# Matric_PCB.net
KiCad netlist of a schematic drawn in EAGLE
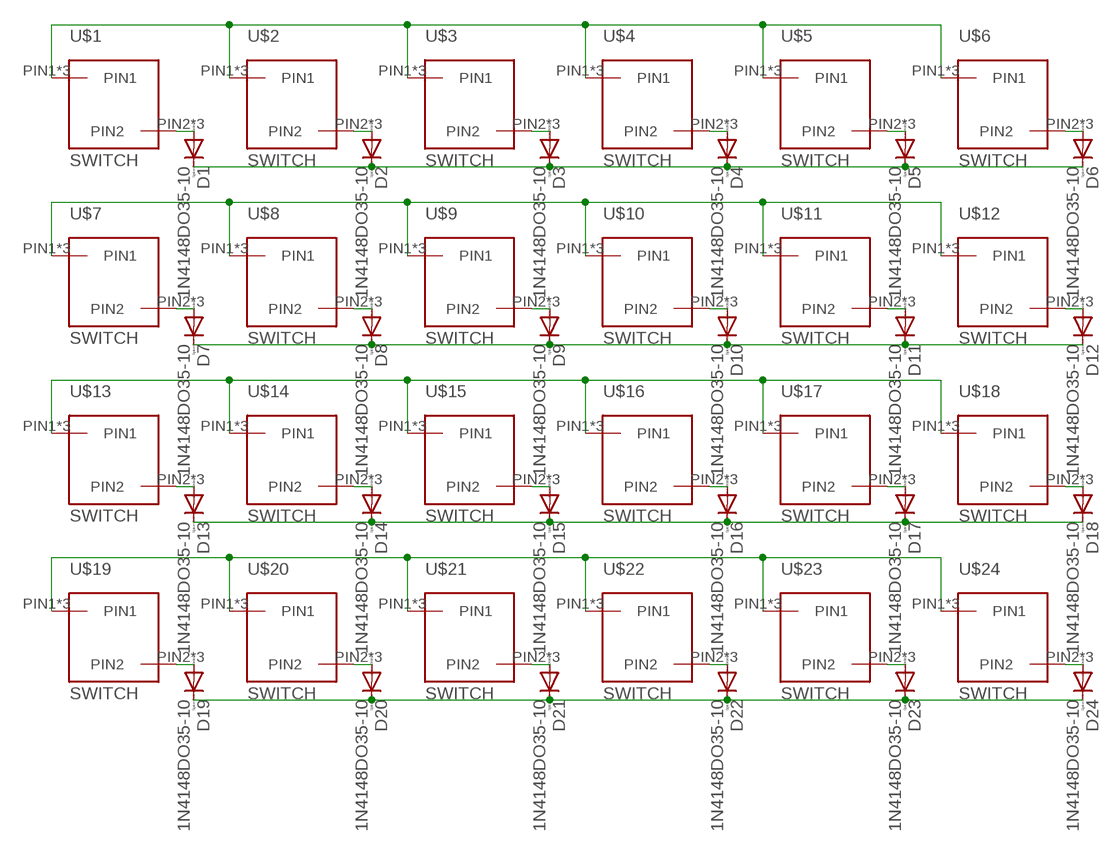
[diagram p0: schematic, sheet 1]

(export (version "E")
  (design (tool "Eeschema 10.0.6"))
  (components
    (comp (ref "D1")
      (value "1N4148DO35-10")
      (footprint "eagle-import:DO35-10")
      (libsource (lib "eagle-import") (part "1N4148DO35-10"))
    )
    (comp (ref "D2")
      (value "1N4148DO35-10")
      (footprint "eagle-import:DO35-10")
      (libsource (lib "eagle-import") (part "1N4148DO35-10"))
    )
    (comp (ref "D3")
      (value "1N4148DO35-10")
      (footprint "eagle-import:DO35-10")
      (libsource (lib "eagle-import") (part "1N4148DO35-10"))
    )
    (comp (ref "D4")
      (value "1N4148DO35-10")
      (footprint "eagle-import:DO35-10")
      (libsource (lib "eagle-import") (part "1N4148DO35-10"))
    )
    (comp (ref "D5")
      (value "1N4148DO35-10")
      (footprint "eagle-import:DO35-10")
      (libsource (lib "eagle-import") (part "1N4148DO35-10"))
    )
    (comp (ref "D6")
      (value "1N4148DO35-10")
      (footprint "eagle-import:DO35-10")
      (libsource (lib "eagle-import") (part "1N4148DO35-10"))
    )
    (comp (ref "D7")
      (value "1N4148DO35-10")
      (footprint "eagle-import:DO35-10")
      (libsource (lib "eagle-import") (part "1N4148DO35-10"))
    )
    (comp (ref "D8")
      (value "1N4148DO35-10")
      (footprint "eagle-import:DO35-10")
      (libsource (lib "eagle-import") (part "1N4148DO35-10"))
    )
    (comp (ref "D9")
      (value "1N4148DO35-10")
      (footprint "eagle-import:DO35-10")
      (libsource (lib "eagle-import") (part "1N4148DO35-10"))
    )
    (comp (ref "D10")
      (value "1N4148DO35-10")
      (footprint "eagle-import:DO35-10")
      (libsource (lib "eagle-import") (part "1N4148DO35-10"))
    )
    (comp (ref "D11")
      (value "1N4148DO35-10")
      (footprint "eagle-import:DO35-10")
      (libsource (lib "eagle-import") (part "1N4148DO35-10"))
    )
    (comp (ref "D12")
      (value "1N4148DO35-10")
      (footprint "eagle-import:DO35-10")
      (libsource (lib "eagle-import") (part "1N4148DO35-10"))
    )
    (comp (ref "D13")
      (value "1N4148DO35-10")
      (footprint "eagle-import:DO35-10")
      (libsource (lib "eagle-import") (part "1N4148DO35-10"))
    )
    (comp (ref "D14")
      (value "1N4148DO35-10")
      (footprint "eagle-import:DO35-10")
      (libsource (lib "eagle-import") (part "1N4148DO35-10"))
    )
    (comp (ref "D15")
      (value "1N4148DO35-10")
      (footprint "eagle-import:DO35-10")
      (libsource (lib "eagle-import") (part "1N4148DO35-10"))
    )
    (comp (ref "D16")
      (value "1N4148DO35-10")
      (footprint "eagle-import:DO35-10")
      (libsource (lib "eagle-import") (part "1N4148DO35-10"))
    )
    (comp (ref "D17")
      (value "1N4148DO35-10")
      (footprint "eagle-import:DO35-10")
      (libsource (lib "eagle-import") (part "1N4148DO35-10"))
    )
    (comp (ref "D18")
      (value "1N4148DO35-10")
      (footprint "eagle-import:DO35-10")
      (libsource (lib "eagle-import") (part "1N4148DO35-10"))
    )
    (comp (ref "D19")
      (value "1N4148DO35-10")
      (footprint "eagle-import:DO35-10")
      (libsource (lib "eagle-import") (part "1N4148DO35-10"))
    )
    (comp (ref "D20")
      (value "1N4148DO35-10")
      (footprint "eagle-import:DO35-10")
      (libsource (lib "eagle-import") (part "1N4148DO35-10"))
    )
    (comp (ref "D21")
      (value "1N4148DO35-10")
      (footprint "eagle-import:DO35-10")
      (libsource (lib "eagle-import") (part "1N4148DO35-10"))
    )
    (comp (ref "D22")
      (value "1N4148DO35-10")
      (footprint "eagle-import:DO35-10")
      (libsource (lib "eagle-import") (part "1N4148DO35-10"))
    )
    (comp (ref "D23")
      (value "1N4148DO35-10")
      (footprint "eagle-import:DO35-10")
      (libsource (lib "eagle-import") (part "1N4148DO35-10"))
    )
    (comp (ref "D24")
      (value "1N4148DO35-10")
      (footprint "eagle-import:DO35-10")
      (libsource (lib "eagle-import") (part "1N4148DO35-10"))
    )
    (comp (ref "U$1")
      (value "SWITCH")
      (footprint "eagle-import:SWITCH")
      (libsource (lib "eagle-import") (part "SWITCH"))
    )
    (comp (ref "U$2")
      (value "SWITCH")
      (footprint "eagle-import:SWITCH")
      (libsource (lib "eagle-import") (part "SWITCH"))
    )
    (comp (ref "U$3")
      (value "SWITCH")
      (footprint "eagle-import:SWITCH")
      (libsource (lib "eagle-import") (part "SWITCH"))
    )
    (comp (ref "U$4")
      (value "SWITCH")
      (footprint "eagle-import:SWITCH")
      (libsource (lib "eagle-import") (part "SWITCH"))
    )
    (comp (ref "U$5")
      (value "SWITCH")
      (footprint "eagle-import:SWITCH")
      (libsource (lib "eagle-import") (part "SWITCH"))
    )
    (comp (ref "U$6")
      (value "SWITCH")
      (footprint "eagle-import:SWITCH")
      (libsource (lib "eagle-import") (part "SWITCH"))
    )
    (comp (ref "U$7")
      (value "SWITCH")
      (footprint "eagle-import:SWITCH")
      (libsource (lib "eagle-import") (part "SWITCH"))
    )
    (comp (ref "U$8")
      (value "SWITCH")
      (footprint "eagle-import:SWITCH")
      (libsource (lib "eagle-import") (part "SWITCH"))
    )
    (comp (ref "U$9")
      (value "SWITCH")
      (footprint "eagle-import:SWITCH")
      (libsource (lib "eagle-import") (part "SWITCH"))
    )
    (comp (ref "U$10")
      (value "SWITCH")
      (footprint "eagle-import:SWITCH")
      (libsource (lib "eagle-import") (part "SWITCH"))
    )
    (comp (ref "U$11")
      (value "SWITCH")
      (footprint "eagle-import:SWITCH")
      (libsource (lib "eagle-import") (part "SWITCH"))
    )
    (comp (ref "U$12")
      (value "SWITCH")
      (footprint "eagle-import:SWITCH")
      (libsource (lib "eagle-import") (part "SWITCH"))
    )
    (comp (ref "U$13")
      (value "SWITCH")
      (footprint "eagle-import:SWITCH")
      (libsource (lib "eagle-import") (part "SWITCH"))
    )
    (comp (ref "U$14")
      (value "SWITCH")
      (footprint "eagle-import:SWITCH")
      (libsource (lib "eagle-import") (part "SWITCH"))
    )
    (comp (ref "U$15")
      (value "SWITCH")
      (footprint "eagle-import:SWITCH")
      (libsource (lib "eagle-import") (part "SWITCH"))
    )
    (comp (ref "U$16")
      (value "SWITCH")
      (footprint "eagle-import:SWITCH")
      (libsource (lib "eagle-import") (part "SWITCH"))
    )
    (comp (ref "U$17")
      (value "SWITCH")
      (footprint "eagle-import:SWITCH")
      (libsource (lib "eagle-import") (part "SWITCH"))
    )
    (comp (ref "U$18")
      (value "SWITCH")
      (footprint "eagle-import:SWITCH")
      (libsource (lib "eagle-import") (part "SWITCH"))
    )
    (comp (ref "U$19")
      (value "SWITCH")
      (footprint "eagle-import:SWITCH")
      (libsource (lib "eagle-import") (part "SWITCH"))
    )
    (comp (ref "U$20")
      (value "SWITCH")
      (footprint "eagle-import:SWITCH")
      (libsource (lib "eagle-import") (part "SWITCH"))
    )
    (comp (ref "U$21")
      (value "SWITCH")
      (footprint "eagle-import:SWITCH")
      (libsource (lib "eagle-import") (part "SWITCH"))
    )
    (comp (ref "U$22")
      (value "SWITCH")
      (footprint "eagle-import:SWITCH")
      (libsource (lib "eagle-import") (part "SWITCH"))
    )
    (comp (ref "U$23")
      (value "SWITCH")
      (footprint "eagle-import:SWITCH")
      (libsource (lib "eagle-import") (part "SWITCH"))
    )
    (comp (ref "U$24")
      (value "SWITCH")
      (footprint "eagle-import:SWITCH")
      (libsource (lib "eagle-import") (part "SWITCH"))
    )
  )
  (nets
    (net (code "1") (name "Net-(D1-PadA)") (class "Default")
      (node (ref "D1") (pin "A") (pinfunction "A_A") (pintype "passive"))
      (node (ref "U$1") (pin "PIN2") (pinfunction "PIN2_PIN2") (pintype "bidirectional"))
      (node (ref "U$1") (pin "PIN2EXT") (pinfunction "PIN2_PIN2EXT") (pintype "bidirectional"))
      (node (ref "U$1") (pin "PIN2MAT") (pinfunction "PIN2_PIN2MAT") (pintype "bidirectional"))
    )
    (net (code "2") (name "Net-(D1-PadC)") (class "Default")
      (node (ref "D1") (pin "C") (pinfunction "C_C") (pintype "passive"))
      (node (ref "D2") (pin "C") (pinfunction "C_C") (pintype "passive"))
      (node (ref "D3") (pin "C") (pinfunction "C_C") (pintype "passive"))
      (node (ref "D4") (pin "C") (pinfunction "C_C") (pintype "passive"))
      (node (ref "D5") (pin "C") (pinfunction "C_C") (pintype "passive"))
      (node (ref "D6") (pin "C") (pinfunction "C_C") (pintype "passive"))
    )
    (net (code "3") (name "Net-(D2-PadA)") (class "Default")
      (node (ref "D2") (pin "A") (pinfunction "A_A") (pintype "passive"))
      (node (ref "U$2") (pin "PIN2") (pinfunction "PIN2_PIN2") (pintype "bidirectional"))
      (node (ref "U$2") (pin "PIN2EXT") (pinfunction "PIN2_PIN2EXT") (pintype "bidirectional"))
      (node (ref "U$2") (pin "PIN2MAT") (pinfunction "PIN2_PIN2MAT") (pintype "bidirectional"))
    )
    (net (code "4") (name "Net-(D3-PadA)") (class "Default")
      (node (ref "D3") (pin "A") (pinfunction "A_A") (pintype "passive"))
      (node (ref "U$3") (pin "PIN2") (pinfunction "PIN2_PIN2") (pintype "bidirectional"))
      (node (ref "U$3") (pin "PIN2EXT") (pinfunction "PIN2_PIN2EXT") (pintype "bidirectional"))
      (node (ref "U$3") (pin "PIN2MAT") (pinfunction "PIN2_PIN2MAT") (pintype "bidirectional"))
    )
    (net (code "5") (name "Net-(D4-PadA)") (class "Default")
      (node (ref "D4") (pin "A") (pinfunction "A_A") (pintype "passive"))
      (node (ref "U$4") (pin "PIN2") (pinfunction "PIN2_PIN2") (pintype "bidirectional"))
      (node (ref "U$4") (pin "PIN2EXT") (pinfunction "PIN2_PIN2EXT") (pintype "bidirectional"))
      (node (ref "U$4") (pin "PIN2MAT") (pinfunction "PIN2_PIN2MAT") (pintype "bidirectional"))
    )
    (net (code "6") (name "Net-(D5-PadA)") (class "Default")
      (node (ref "D5") (pin "A") (pinfunction "A_A") (pintype "passive"))
      (node (ref "U$5") (pin "PIN2") (pinfunction "PIN2_PIN2") (pintype "bidirectional"))
      (node (ref "U$5") (pin "PIN2EXT") (pinfunction "PIN2_PIN2EXT") (pintype "bidirectional"))
      (node (ref "U$5") (pin "PIN2MAT") (pinfunction "PIN2_PIN2MAT") (pintype "bidirectional"))
    )
    (net (code "7") (name "Net-(D6-PadA)") (class "Default")
      (node (ref "D6") (pin "A") (pinfunction "A_A") (pintype "passive"))
      (node (ref "U$6") (pin "PIN2") (pinfunction "PIN2_PIN2") (pintype "bidirectional"))
      (node (ref "U$6") (pin "PIN2EXT") (pinfunction "PIN2_PIN2EXT") (pintype "bidirectional"))
      (node (ref "U$6") (pin "PIN2MAT") (pinfunction "PIN2_PIN2MAT") (pintype "bidirectional"))
    )
    (net (code "8") (name "Net-(D7-PadA)") (class "Default")
      (node (ref "D7") (pin "A") (pinfunction "A_A") (pintype "passive"))
      (node (ref "U$7") (pin "PIN2") (pinfunction "PIN2_PIN2") (pintype "bidirectional"))
      (node (ref "U$7") (pin "PIN2EXT") (pinfunction "PIN2_PIN2EXT") (pintype "bidirectional"))
      (node (ref "U$7") (pin "PIN2MAT") (pinfunction "PIN2_PIN2MAT") (pintype "bidirectional"))
    )
    (net (code "9") (name "Net-(D8-PadA)") (class "Default")
      (node (ref "D8") (pin "A") (pinfunction "A_A") (pintype "passive"))
      (node (ref "U$8") (pin "PIN2") (pinfunction "PIN2_PIN2") (pintype "bidirectional"))
      (node (ref "U$8") (pin "PIN2EXT") (pinfunction "PIN2_PIN2EXT") (pintype "bidirectional"))
      (node (ref "U$8") (pin "PIN2MAT") (pinfunction "PIN2_PIN2MAT") (pintype "bidirectional"))
    )
    (net (code "10") (name "Net-(D9-PadA)") (class "Default")
      (node (ref "D9") (pin "A") (pinfunction "A_A") (pintype "passive"))
      (node (ref "U$9") (pin "PIN2") (pinfunction "PIN2_PIN2") (pintype "bidirectional"))
      (node (ref "U$9") (pin "PIN2EXT") (pinfunction "PIN2_PIN2EXT") (pintype "bidirectional"))
      (node (ref "U$9") (pin "PIN2MAT") (pinfunction "PIN2_PIN2MAT") (pintype "bidirectional"))
    )
    (net (code "11") (name "Net-(D10-PadA)") (class "Default")
      (node (ref "D10") (pin "A") (pinfunction "A_A") (pintype "passive"))
      (node (ref "U$10") (pin "PIN2") (pinfunction "PIN2_PIN2") (pintype "bidirectional"))
      (node (ref "U$10") (pin "PIN2EXT") (pinfunction "PIN2_PIN2EXT") (pintype "bidirectional"))
      (node (ref "U$10") (pin "PIN2MAT") (pinfunction "PIN2_PIN2MAT") (pintype "bidirectional"))
    )
    (net (code "12") (name "Net-(D10-PadC)") (class "Default")
      (node (ref "D10") (pin "C") (pinfunction "C_C") (pintype "passive"))
      (node (ref "D11") (pin "C") (pinfunction "C_C") (pintype "passive"))
      (node (ref "D12") (pin "C") (pinfunction "C_C") (pintype "passive"))
      (node (ref "D7") (pin "C") (pinfunction "C_C") (pintype "passive"))
      (node (ref "D8") (pin "C") (pinfunction "C_C") (pintype "passive"))
      (node (ref "D9") (pin "C") (pinfunction "C_C") (pintype "passive"))
    )
    (net (code "13") (name "Net-(D11-PadA)") (class "Default")
      (node (ref "D11") (pin "A") (pinfunction "A_A") (pintype "passive"))
      (node (ref "U$11") (pin "PIN2") (pinfunction "PIN2_PIN2") (pintype "bidirectional"))
      (node (ref "U$11") (pin "PIN2EXT") (pinfunction "PIN2_PIN2EXT") (pintype "bidirectional"))
      (node (ref "U$11") (pin "PIN2MAT") (pinfunction "PIN2_PIN2MAT") (pintype "bidirectional"))
    )
    (net (code "14") (name "Net-(D12-PadA)") (class "Default")
      (node (ref "D12") (pin "A") (pinfunction "A_A") (pintype "passive"))
      (node (ref "U$12") (pin "PIN2") (pinfunction "PIN2_PIN2") (pintype "bidirectional"))
      (node (ref "U$12") (pin "PIN2EXT") (pinfunction "PIN2_PIN2EXT") (pintype "bidirectional"))
      (node (ref "U$12") (pin "PIN2MAT") (pinfunction "PIN2_PIN2MAT") (pintype "bidirectional"))
    )
    (net (code "15") (name "Net-(D13-PadA)") (class "Default")
      (node (ref "D13") (pin "A") (pinfunction "A_A") (pintype "passive"))
      (node (ref "U$13") (pin "PIN2") (pinfunction "PIN2_PIN2") (pintype "bidirectional"))
      (node (ref "U$13") (pin "PIN2EXT") (pinfunction "PIN2_PIN2EXT") (pintype "bidirectional"))
      (node (ref "U$13") (pin "PIN2MAT") (pinfunction "PIN2_PIN2MAT") (pintype "bidirectional"))
    )
    (net (code "16") (name "Net-(D13-PadC)") (class "Default")
      (node (ref "D13") (pin "C") (pinfunction "C_C") (pintype "passive"))
      (node (ref "D14") (pin "C") (pinfunction "C_C") (pintype "passive"))
      (node (ref "D15") (pin "C") (pinfunction "C_C") (pintype "passive"))
      (node (ref "D16") (pin "C") (pinfunction "C_C") (pintype "passive"))
      (node (ref "D17") (pin "C") (pinfunction "C_C") (pintype "passive"))
      (node (ref "D18") (pin "C") (pinfunction "C_C") (pintype "passive"))
    )
    (net (code "17") (name "Net-(D14-PadA)") (class "Default")
      (node (ref "D14") (pin "A") (pinfunction "A_A") (pintype "passive"))
      (node (ref "U$14") (pin "PIN2") (pinfunction "PIN2_PIN2") (pintype "bidirectional"))
      (node (ref "U$14") (pin "PIN2EXT") (pinfunction "PIN2_PIN2EXT") (pintype "bidirectional"))
      (node (ref "U$14") (pin "PIN2MAT") (pinfunction "PIN2_PIN2MAT") (pintype "bidirectional"))
    )
    (net (code "18") (name "Net-(D15-PadA)") (class "Default")
      (node (ref "D15") (pin "A") (pinfunction "A_A") (pintype "passive"))
      (node (ref "U$15") (pin "PIN2") (pinfunction "PIN2_PIN2") (pintype "bidirectional"))
      (node (ref "U$15") (pin "PIN2EXT") (pinfunction "PIN2_PIN2EXT") (pintype "bidirectional"))
      (node (ref "U$15") (pin "PIN2MAT") (pinfunction "PIN2_PIN2MAT") (pintype "bidirectional"))
    )
    (net (code "19") (name "Net-(D16-PadA)") (class "Default")
      (node (ref "D16") (pin "A") (pinfunction "A_A") (pintype "passive"))
      (node (ref "U$16") (pin "PIN2") (pinfunction "PIN2_PIN2") (pintype "bidirectional"))
      (node (ref "U$16") (pin "PIN2EXT") (pinfunction "PIN2_PIN2EXT") (pintype "bidirectional"))
      (node (ref "U$16") (pin "PIN2MAT") (pinfunction "PIN2_PIN2MAT") (pintype "bidirectional"))
    )
    (net (code "20") (name "Net-(D17-PadA)") (class "Default")
      (node (ref "D17") (pin "A") (pinfunction "A_A") (pintype "passive"))
      (node (ref "U$17") (pin "PIN2") (pinfunction "PIN2_PIN2") (pintype "bidirectional"))
      (node (ref "U$17") (pin "PIN2EXT") (pinfunction "PIN2_PIN2EXT") (pintype "bidirectional"))
      (node (ref "U$17") (pin "PIN2MAT") (pinfunction "PIN2_PIN2MAT") (pintype "bidirectional"))
    )
    (net (code "21") (name "Net-(D18-PadA)") (class "Default")
      (node (ref "D18") (pin "A") (pinfunction "A_A") (pintype "passive"))
      (node (ref "U$18") (pin "PIN2") (pinfunction "PIN2_PIN2") (pintype "bidirectional"))
      (node (ref "U$18") (pin "PIN2EXT") (pinfunction "PIN2_PIN2EXT") (pintype "bidirectional"))
      (node (ref "U$18") (pin "PIN2MAT") (pinfunction "PIN2_PIN2MAT") (pintype "bidirectional"))
    )
    (net (code "22") (name "Net-(D19-PadA)") (class "Default")
      (node (ref "D19") (pin "A") (pinfunction "A_A") (pintype "passive"))
      (node (ref "U$19") (pin "PIN2") (pinfunction "PIN2_PIN2") (pintype "bidirectional"))
      (node (ref "U$19") (pin "PIN2EXT") (pinfunction "PIN2_PIN2EXT") (pintype "bidirectional"))
      (node (ref "U$19") (pin "PIN2MAT") (pinfunction "PIN2_PIN2MAT") (pintype "bidirectional"))
    )
    (net (code "23") (name "Net-(D19-PadC)") (class "Default")
      (node (ref "D19") (pin "C") (pinfunction "C_C") (pintype "passive"))
      (node (ref "D20") (pin "C") (pinfunction "C_C") (pintype "passive"))
      (node (ref "D21") (pin "C") (pinfunction "C_C") (pintype "passive"))
      (node (ref "D22") (pin "C") (pinfunction "C_C") (pintype "passive"))
      (node (ref "D23") (pin "C") (pinfunction "C_C") (pintype "passive"))
      (node (ref "D24") (pin "C") (pinfunction "C_C") (pintype "passive"))
    )
    (net (code "24") (name "Net-(D20-PadA)") (class "Default")
      (node (ref "D20") (pin "A") (pinfunction "A_A") (pintype "passive"))
      (node (ref "U$20") (pin "PIN2") (pinfunction "PIN2_PIN2") (pintype "bidirectional"))
      (node (ref "U$20") (pin "PIN2EXT") (pinfunction "PIN2_PIN2EXT") (pintype "bidirectional"))
      (node (ref "U$20") (pin "PIN2MAT") (pinfunction "PIN2_PIN2MAT") (pintype "bidirectional"))
    )
    (net (code "25") (name "Net-(D21-PadA)") (class "Default")
      (node (ref "D21") (pin "A") (pinfunction "A_A") (pintype "passive"))
      (node (ref "U$21") (pin "PIN2") (pinfunction "PIN2_PIN2") (pintype "bidirectional"))
      (node (ref "U$21") (pin "PIN2EXT") (pinfunction "PIN2_PIN2EXT") (pintype "bidirectional"))
      (node (ref "U$21") (pin "PIN2MAT") (pinfunction "PIN2_PIN2MAT") (pintype "bidirectional"))
    )
    (net (code "26") (name "Net-(D22-PadA)") (class "Default")
      (node (ref "D22") (pin "A") (pinfunction "A_A") (pintype "passive"))
      (node (ref "U$22") (pin "PIN2") (pinfunction "PIN2_PIN2") (pintype "bidirectional"))
      (node (ref "U$22") (pin "PIN2EXT") (pinfunction "PIN2_PIN2EXT") (pintype "bidirectional"))
      (node (ref "U$22") (pin "PIN2MAT") (pinfunction "PIN2_PIN2MAT") (pintype "bidirectional"))
    )
    (net (code "27") (name "Net-(D23-PadA)") (class "Default")
      (node (ref "D23") (pin "A") (pinfunction "A_A") (pintype "passive"))
      (node (ref "U$23") (pin "PIN2") (pinfunction "PIN2_PIN2") (pintype "bidirectional"))
      (node (ref "U$23") (pin "PIN2EXT") (pinfunction "PIN2_PIN2EXT") (pintype "bidirectional"))
      (node (ref "U$23") (pin "PIN2MAT") (pinfunction "PIN2_PIN2MAT") (pintype "bidirectional"))
    )
    (net (code "28") (name "Net-(D24-PadA)") (class "Default")
      (node (ref "D24") (pin "A") (pinfunction "A_A") (pintype "passive"))
      (node (ref "U$24") (pin "PIN2") (pinfunction "PIN2_PIN2") (pintype "bidirectional"))
      (node (ref "U$24") (pin "PIN2EXT") (pinfunction "PIN2_PIN2EXT") (pintype "bidirectional"))
      (node (ref "U$24") (pin "PIN2MAT") (pinfunction "PIN2_PIN2MAT") (pintype "bidirectional"))
    )
    (net (code "29") (name "Net-(U$1-PIN1-PadPIN1EXTX)") (class "Default")
      (node (ref "U$1") (pin "PIN1") (pinfunction "PIN1_PIN1") (pintype "bidirectional"))
      (node (ref "U$1") (pin "PIN1EXTX") (pinfunction "PIN1_PIN1EXTX") (pintype "bidirectional"))
      (node (ref "U$1") (pin "PIN1MAT") (pinfunction "PIN1_PIN1MAT") (pintype "bidirectional"))
      (node (ref "U$2") (pin "PIN1") (pinfunction "PIN1_PIN1") (pintype "bidirectional"))
      (node (ref "U$2") (pin "PIN1EXTX") (pinfunction "PIN1_PIN1EXTX") (pintype "bidirectional"))
      (node (ref "U$2") (pin "PIN1MAT") (pinfunction "PIN1_PIN1MAT") (pintype "bidirectional"))
      (node (ref "U$3") (pin "PIN1") (pinfunction "PIN1_PIN1") (pintype "bidirectional"))
      (node (ref "U$3") (pin "PIN1EXTX") (pinfunction "PIN1_PIN1EXTX") (pintype "bidirectional"))
      (node (ref "U$3") (pin "PIN1MAT") (pinfunction "PIN1_PIN1MAT") (pintype "bidirectional"))
      (node (ref "U$4") (pin "PIN1") (pinfunction "PIN1_PIN1") (pintype "bidirectional"))
      (node (ref "U$4") (pin "PIN1EXTX") (pinfunction "PIN1_PIN1EXTX") (pintype "bidirectional"))
      (node (ref "U$4") (pin "PIN1MAT") (pinfunction "PIN1_PIN1MAT") (pintype "bidirectional"))
      (node (ref "U$5") (pin "PIN1") (pinfunction "PIN1_PIN1") (pintype "bidirectional"))
      (node (ref "U$5") (pin "PIN1EXTX") (pinfunction "PIN1_PIN1EXTX") (pintype "bidirectional"))
      (node (ref "U$5") (pin "PIN1MAT") (pinfunction "PIN1_PIN1MAT") (pintype "bidirectional"))
      (node (ref "U$6") (pin "PIN1") (pinfunction "PIN1_PIN1") (pintype "bidirectional"))
      (node (ref "U$6") (pin "PIN1EXTX") (pinfunction "PIN1_PIN1EXTX") (pintype "bidirectional"))
      (node (ref "U$6") (pin "PIN1MAT") (pinfunction "PIN1_PIN1MAT") (pintype "bidirectional"))
    )
    (net (code "30") (name "Net-(U$10-PIN1-PadPIN1EXTX)") (class "Default")
      (node (ref "U$10") (pin "PIN1") (pinfunction "PIN1_PIN1") (pintype "bidirectional"))
      (node (ref "U$10") (pin "PIN1EXTX") (pinfunction "PIN1_PIN1EXTX") (pintype "bidirectional"))
      (node (ref "U$10") (pin "PIN1MAT") (pinfunction "PIN1_PIN1MAT") (pintype "bidirectional"))
      (node (ref "U$11") (pin "PIN1") (pinfunction "PIN1_PIN1") (pintype "bidirectional"))
      (node (ref "U$11") (pin "PIN1EXTX") (pinfunction "PIN1_PIN1EXTX") (pintype "bidirectional"))
      (node (ref "U$11") (pin "PIN1MAT") (pinfunction "PIN1_PIN1MAT") (pintype "bidirectional"))
      (node (ref "U$12") (pin "PIN1") (pinfunction "PIN1_PIN1") (pintype "bidirectional"))
      (node (ref "U$12") (pin "PIN1EXTX") (pinfunction "PIN1_PIN1EXTX") (pintype "bidirectional"))
      (node (ref "U$12") (pin "PIN1MAT") (pinfunction "PIN1_PIN1MAT") (pintype "bidirectional"))
      (node (ref "U$7") (pin "PIN1") (pinfunction "PIN1_PIN1") (pintype "bidirectional"))
      (node (ref "U$7") (pin "PIN1EXTX") (pinfunction "PIN1_PIN1EXTX") (pintype "bidirectional"))
      (node (ref "U$7") (pin "PIN1MAT") (pinfunction "PIN1_PIN1MAT") (pintype "bidirectional"))
      (node (ref "U$8") (pin "PIN1") (pinfunction "PIN1_PIN1") (pintype "bidirectional"))
      (node (ref "U$8") (pin "PIN1EXTX") (pinfunction "PIN1_PIN1EXTX") (pintype "bidirectional"))
      (node (ref "U$8") (pin "PIN1MAT") (pinfunction "PIN1_PIN1MAT") (pintype "bidirectional"))
      (node (ref "U$9") (pin "PIN1") (pinfunction "PIN1_PIN1") (pintype "bidirectional"))
      (node (ref "U$9") (pin "PIN1EXTX") (pinfunction "PIN1_PIN1EXTX") (pintype "bidirectional"))
      (node (ref "U$9") (pin "PIN1MAT") (pinfunction "PIN1_PIN1MAT") (pintype "bidirectional"))
    )
    (net (code "31") (name "Net-(U$13-PIN1-PadPIN1EXTX)") (class "Default")
      (node (ref "U$13") (pin "PIN1") (pinfunction "PIN1_PIN1") (pintype "bidirectional"))
      (node (ref "U$13") (pin "PIN1EXTX") (pinfunction "PIN1_PIN1EXTX") (pintype "bidirectional"))
      (node (ref "U$13") (pin "PIN1MAT") (pinfunction "PIN1_PIN1MAT") (pintype "bidirectional"))
      (node (ref "U$14") (pin "PIN1") (pinfunction "PIN1_PIN1") (pintype "bidirectional"))
      (node (ref "U$14") (pin "PIN1EXTX") (pinfunction "PIN1_PIN1EXTX") (pintype "bidirectional"))
      (node (ref "U$14") (pin "PIN1MAT") (pinfunction "PIN1_PIN1MAT") (pintype "bidirectional"))
      (node (ref "U$15") (pin "PIN1") (pinfunction "PIN1_PIN1") (pintype "bidirectional"))
      (node (ref "U$15") (pin "PIN1EXTX") (pinfunction "PIN1_PIN1EXTX") (pintype "bidirectional"))
      (node (ref "U$15") (pin "PIN1MAT") (pinfunction "PIN1_PIN1MAT") (pintype "bidirectional"))
      (node (ref "U$16") (pin "PIN1") (pinfunction "PIN1_PIN1") (pintype "bidirectional"))
      (node (ref "U$16") (pin "PIN1EXTX") (pinfunction "PIN1_PIN1EXTX") (pintype "bidirectional"))
      (node (ref "U$16") (pin "PIN1MAT") (pinfunction "PIN1_PIN1MAT") (pintype "bidirectional"))
      (node (ref "U$17") (pin "PIN1") (pinfunction "PIN1_PIN1") (pintype "bidirectional"))
      (node (ref "U$17") (pin "PIN1EXTX") (pinfunction "PIN1_PIN1EXTX") (pintype "bidirectional"))
      (node (ref "U$17") (pin "PIN1MAT") (pinfunction "PIN1_PIN1MAT") (pintype "bidirectional"))
      (node (ref "U$18") (pin "PIN1") (pinfunction "PIN1_PIN1") (pintype "bidirectional"))
      (node (ref "U$18") (pin "PIN1EXTX") (pinfunction "PIN1_PIN1EXTX") (pintype "bidirectional"))
      (node (ref "U$18") (pin "PIN1MAT") (pinfunction "PIN1_PIN1MAT") (pintype "bidirectional"))
    )
    (net (code "32") (name "Net-(U$19-PIN1-PadPIN1EXTX)") (class "Default")
      (node (ref "U$19") (pin "PIN1") (pinfunction "PIN1_PIN1") (pintype "bidirectional"))
      (node (ref "U$19") (pin "PIN1EXTX") (pinfunction "PIN1_PIN1EXTX") (pintype "bidirectional"))
      (node (ref "U$19") (pin "PIN1MAT") (pinfunction "PIN1_PIN1MAT") (pintype "bidirectional"))
      (node (ref "U$20") (pin "PIN1") (pinfunction "PIN1_PIN1") (pintype "bidirectional"))
      (node (ref "U$20") (pin "PIN1EXTX") (pinfunction "PIN1_PIN1EXTX") (pintype "bidirectional"))
      (node (ref "U$20") (pin "PIN1MAT") (pinfunction "PIN1_PIN1MAT") (pintype "bidirectional"))
      (node (ref "U$21") (pin "PIN1") (pinfunction "PIN1_PIN1") (pintype "bidirectional"))
      (node (ref "U$21") (pin "PIN1EXTX") (pinfunction "PIN1_PIN1EXTX") (pintype "bidirectional"))
      (node (ref "U$21") (pin "PIN1MAT") (pinfunction "PIN1_PIN1MAT") (pintype "bidirectional"))
      (node (ref "U$22") (pin "PIN1") (pinfunction "PIN1_PIN1") (pintype "bidirectional"))
      (node (ref "U$22") (pin "PIN1EXTX") (pinfunction "PIN1_PIN1EXTX") (pintype "bidirectional"))
      (node (ref "U$22") (pin "PIN1MAT") (pinfunction "PIN1_PIN1MAT") (pintype "bidirectional"))
      (node (ref "U$23") (pin "PIN1") (pinfunction "PIN1_PIN1") (pintype "bidirectional"))
      (node (ref "U$23") (pin "PIN1EXTX") (pinfunction "PIN1_PIN1EXTX") (pintype "bidirectional"))
      (node (ref "U$23") (pin "PIN1MAT") (pinfunction "PIN1_PIN1MAT") (pintype "bidirectional"))
      (node (ref "U$24") (pin "PIN1") (pinfunction "PIN1_PIN1") (pintype "bidirectional"))
      (node (ref "U$24") (pin "PIN1EXTX") (pinfunction "PIN1_PIN1EXTX") (pintype "bidirectional"))
      (node (ref "U$24") (pin "PIN1MAT") (pinfunction "PIN1_PIN1MAT") (pintype "bidirectional"))
    )
  )
)
